# CathodeControl.net
KiCad netlist of a schematic drawn in Altium Designer
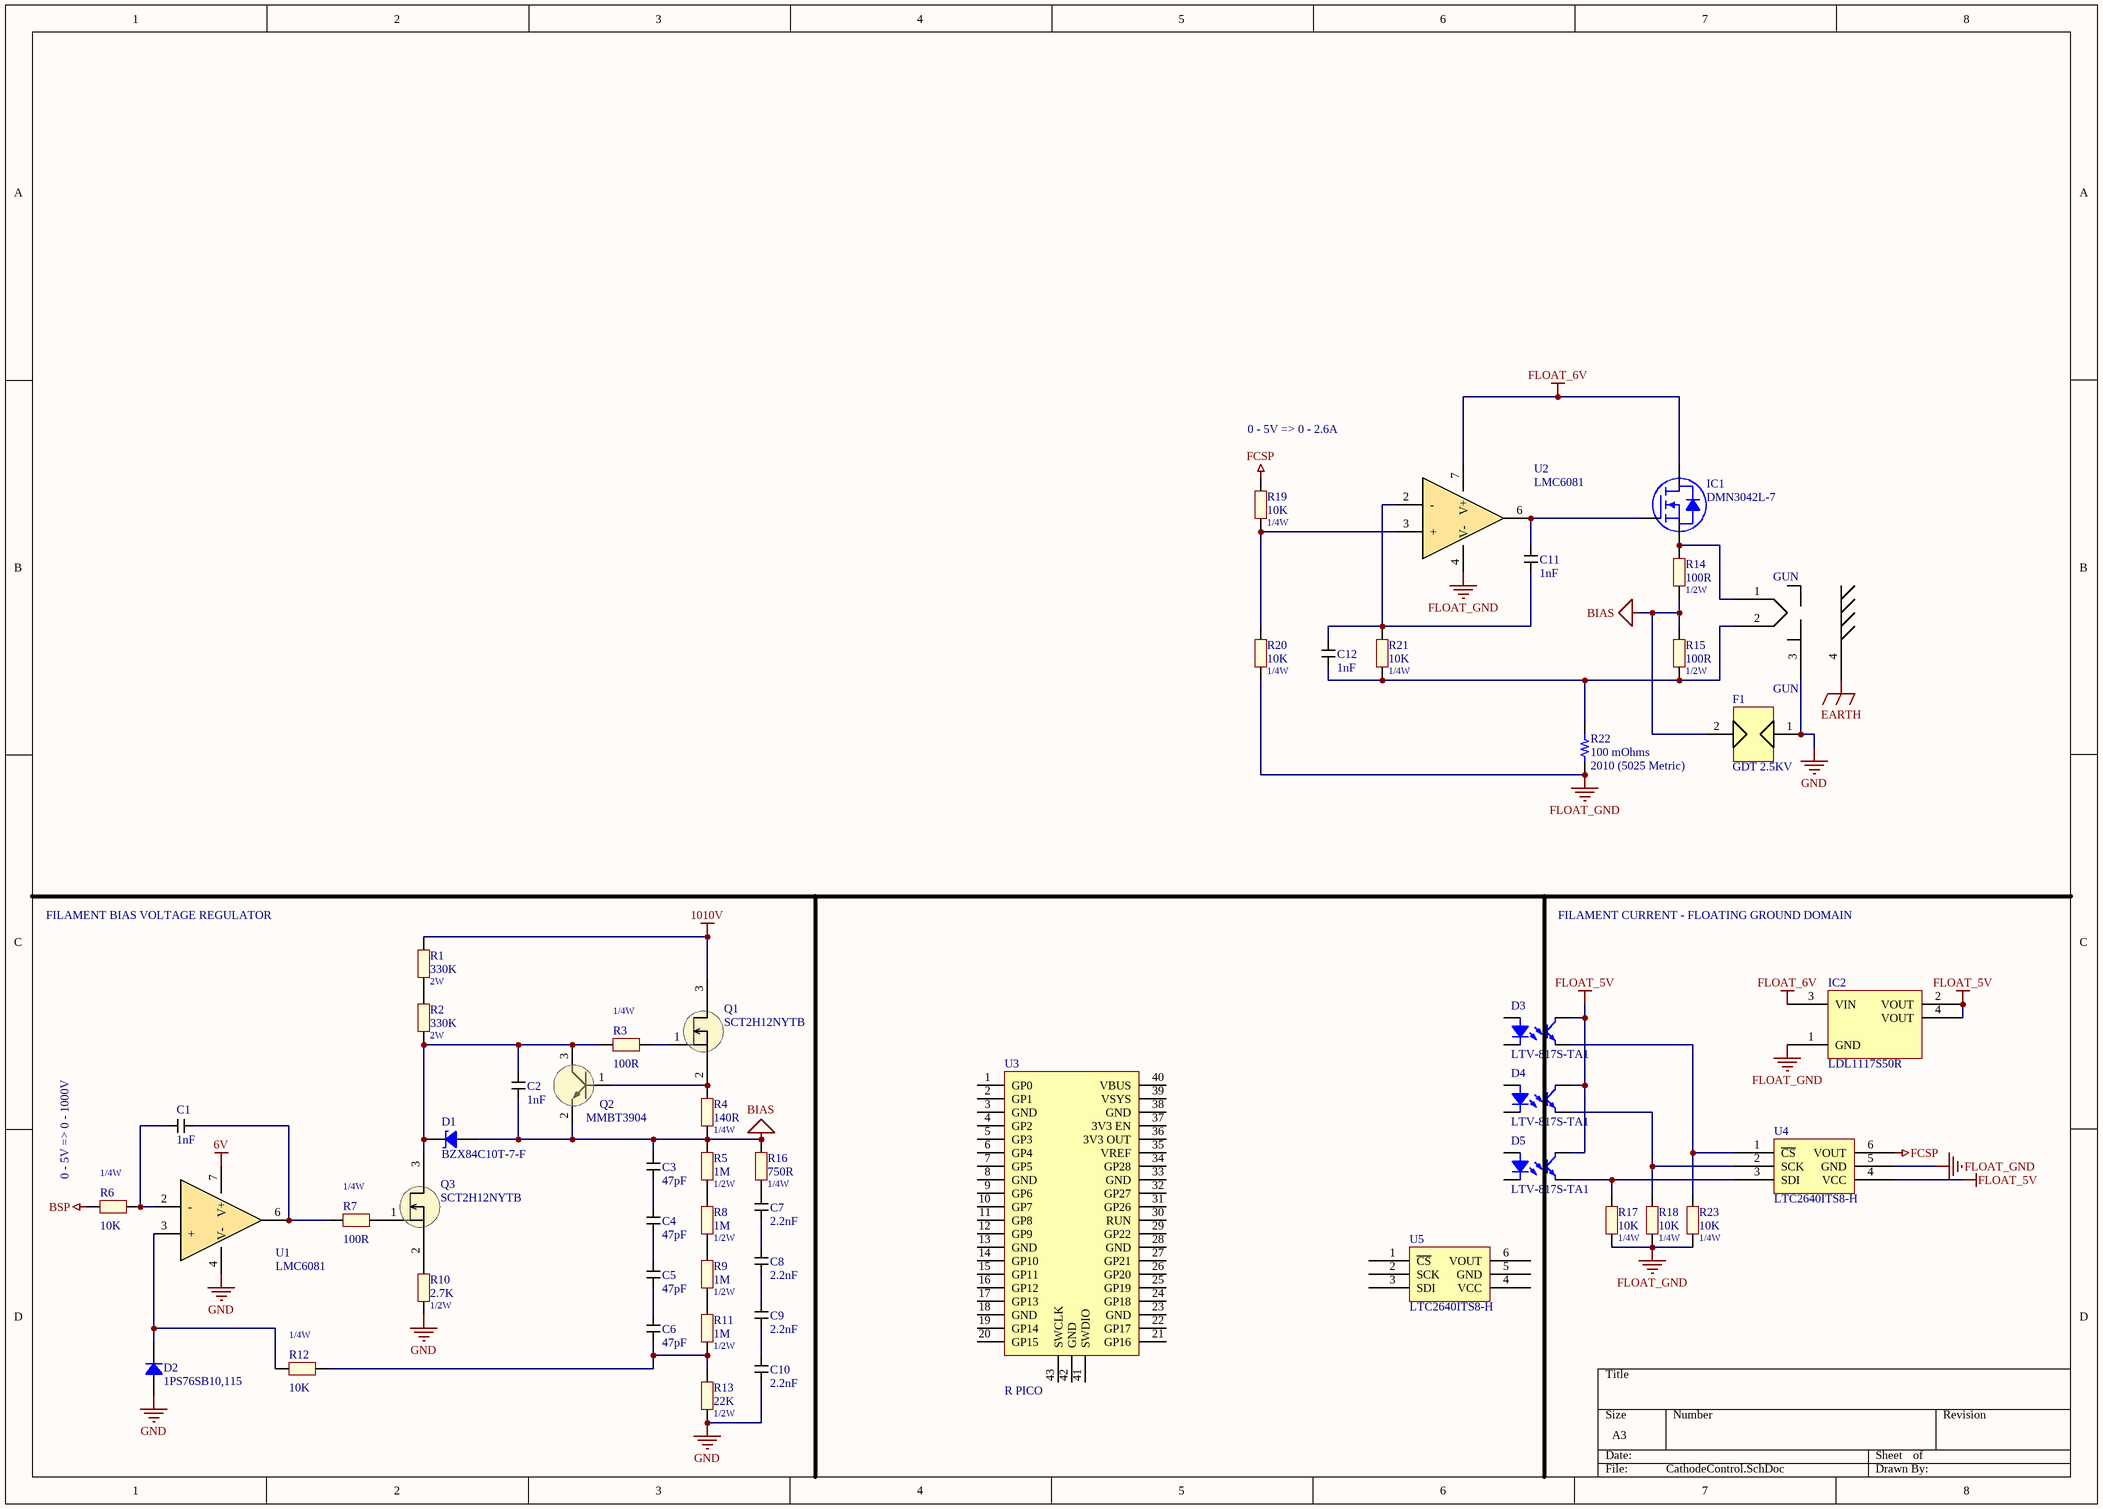
[diagram p0: CathodeControl.SchDoc]

(export (version "E")
  (design (tool "Eeschema 10.0.6"))
  (components
    (comp (ref "C1") (value "1nF") (footprint "C0805") (libsource (lib "VinisLab") (part "C0805")))
    (comp (ref "C2") (value "1nF") (footprint "C0805") (libsource (lib "VinisLab") (part "C0805")))
    (comp (ref "C3")
      (value "47pF")
      (footprint "C0805")
      (description "47 pF ±5% 500V Ceramic Capacitor C0G, NP0 0805 (2012 Metric)")
      (libsource (lib "VinisLab") (part "885342007006"))
    )
    (comp (ref "C4")
      (value "47pF")
      (footprint "C0805")
      (description "47 pF ±5% 500V Ceramic Capacitor C0G, NP0 0805 (2012 Metric)")
      (libsource (lib "VinisLab") (part "885342007006"))
    )
    (comp (ref "C5")
      (value "47pF")
      (footprint "C0805")
      (description "47 pF ±5% 500V Ceramic Capacitor C0G, NP0 0805 (2012 Metric)")
      (libsource (lib "VinisLab") (part "885342007006"))
    )
    (comp (ref "C6")
      (value "47pF")
      (footprint "C0805")
      (description "47 pF ±5% 500V Ceramic Capacitor C0G, NP0 0805 (2012 Metric)")
      (libsource (lib "VinisLab") (part "885342007006"))
    )
    (comp (ref "C7") (value "2.2nF") (footprint "C0805") (libsource (lib "VinisLab") (part "C0805")))
    (comp (ref "C8") (value "2.2nF") (footprint "C0805") (libsource (lib "VinisLab") (part "C0805")))
    (comp (ref "C9") (value "2.2nF") (footprint "C0805") (libsource (lib "VinisLab") (part "C0805")))
    (comp (ref "C10") (value "2.2nF") (footprint "C0805") (libsource (lib "VinisLab") (part "C0805")))
    (comp (ref "C11") (value "1nF") (footprint "C0805") (libsource (lib "VinisLab") (part "C0805")))
    (comp (ref "C12") (value "1nF") (footprint "C0805") (libsource (lib "VinisLab") (part "C0805")))
    (comp (ref "D1")
      (value "BZX84C10T-7-F")
      (footprint "DIODES SOT-523")
      (description "DIODE ZENER 10V 150MW SOT523")
      (fields (field (name "MANUFACTURER") "Diodes Incorporated") (field (name "TOLERANCE") "±6%"))
      (libsource (lib "Cel") (part "Diode Zener"))
    )
    (comp (ref "D2")
      (value "1PS76SB10,115")
      (footprint "SOD323")
      (description "DIODE SCHOTTKY 30V 200MA SOD323")
      (fields (field (name "MANUFACTURER") "Nexperia USA Inc."))
      (libsource (lib "Cel") (part "Diode"))
    )
    (comp (ref "D3")
      (value "LTV-817S-TA1")
      (footprint "LITEON LTV-817")
      (description "OPTOISOLATR 5KV TRANSISTOR 4-SMD")
      (fields (field (name "MANUFACTURER") "Lite-On Inc."))
      (libsource (lib "Cel") (part "Optoisolator"))
    )
    (comp (ref "D4")
      (value "LTV-817S-TA1")
      (footprint "LITEON LTV-817")
      (description "OPTOISOLATR 5KV TRANSISTOR 4-SMD")
      (fields (field (name "MANUFACTURER") "Lite-On Inc."))
      (libsource (lib "Cel") (part "Optoisolator"))
    )
    (comp (ref "D5")
      (value "LTV-817S-TA1")
      (footprint "LITEON LTV-817")
      (description "OPTOISOLATR 5KV TRANSISTOR 4-SMD")
      (fields (field (name "MANUFACTURER") "Lite-On Inc."))
      (libsource (lib "Cel") (part "Optoisolator"))
    )
    (comp (ref "F1")
      (value "GDT 2.5KV")
      (footprint "GDT")
      (description "Gas Discharge Tube 2500 V 2000A (2kA) ±20% 2 Pole Through Hole")
      (libsource (lib "VinisLab") (part "B88069X2500T502"))
    )
    (comp (ref "GUN") (value "GUN") (libsource (lib "VinisLab") (part "GUN")))
    (comp (ref "IC1")
      (value "DMN3042L-7")
      (footprint "DIODES SOT-23-3")
      (description "MOSFET N-CH 30V 5.8A SOT23")
      (fields (field (name "MANUFACTURER") "Diodes Incorporated"))
      (libsource (lib "Cel") (part "DIODES INC MOSFET N-CH SOT-23-3"))
    )
    (comp (ref "IC2")
      (value "LDL1117S50R")
      (footprint "ST SOT-223")
      (description "IC REG LINEAR 5V 1.2A SOT223")
      (fields (field (name "MANUFACTURER") "STMicroelectronics"))
      (libsource (lib "Cel") (part "ST LDL1117"))
    )
    (comp (ref "Q1")
      (value "SCT2H12NYTB")
      (footprint "TO-268-2L")
      (description "N-MOSFET 1700V 4A")
      (libsource (lib "VinisLab") (part "SCT2H12NYTB"))
    )
    (comp (ref "Q2")
      (value "MMBT3904")
      (footprint "SOT-23-3")
      (description "BIPOLAR NPN Transistor")
      (libsource (lib "VinisLab") (part "MMBT3904_1"))
    )
    (comp (ref "Q3")
      (value "SCT2H12NYTB")
      (footprint "TO-268-2L")
      (description "N-MOSFET 1700V 4A")
      (libsource (lib "VinisLab") (part "SCT2H12NYTB"))
    )
    (comp (ref "R1")
      (value "330K")
      (footprint "R2512")
      (description "Resistor 2W")
      (fields (field (name "POWER") "2W"))
      (libsource (lib "VinisLab") (part "R2W"))
    )
    (comp (ref "R2")
      (value "330K")
      (footprint "R2512")
      (description "Resistor 2W")
      (fields (field (name "POWER") "2W"))
      (libsource (lib "VinisLab") (part "R2W"))
    )
    (comp (ref "R3")
      (value "100R")
      (footprint "R0805")
      (description "Resistor 1/2W")
      (fields (field (name "POWER") "1/4W"))
      (libsource (lib "") (part "R0.25W_2"))
    )
    (comp (ref "R4")
      (value "140R")
      (footprint "R0805")
      (description "Resistor 1/2W")
      (fields (field (name "POWER") "1/4W"))
      (libsource (lib "") (part "R0.25W_1"))
    )
    (comp (ref "R5")
      (value "1M")
      (footprint "R1206")
      (description "Resistor 1/2W")
      (fields (field (name "POWER") "1/2W"))
      (libsource (lib "VinisLab") (part "R0.5W"))
    )
    (comp (ref "R6")
      (value "10K")
      (footprint "R0805")
      (description "Resistor 1/2W")
      (fields (field (name "POWER") "1/4W"))
      (libsource (lib "") (part "R0.25W_2"))
    )
    (comp (ref "R7")
      (value "100R")
      (footprint "R0805")
      (description "Resistor 1/2W")
      (fields (field (name "POWER") "1/4W"))
      (libsource (lib "") (part "R0.25W_2"))
    )
    (comp (ref "R8")
      (value "1M")
      (footprint "R1206")
      (description "Resistor 1/2W")
      (fields (field (name "POWER") "1/2W"))
      (libsource (lib "VinisLab") (part "R0.5W"))
    )
    (comp (ref "R9")
      (value "1M")
      (footprint "R1206")
      (description "Resistor 1/2W")
      (fields (field (name "POWER") "1/2W"))
      (libsource (lib "VinisLab") (part "R0.5W"))
    )
    (comp (ref "R10")
      (value "2.7K")
      (footprint "R1206")
      (description "Resistor 1/2W")
      (fields (field (name "POWER") "1/2W"))
      (libsource (lib "VinisLab") (part "R0.5W"))
    )
    (comp (ref "R11")
      (value "1M")
      (footprint "R1206")
      (description "Resistor 1/2W")
      (fields (field (name "POWER") "1/2W"))
      (libsource (lib "VinisLab") (part "R0.5W"))
    )
    (comp (ref "R12")
      (value "10K")
      (footprint "R0805")
      (description "Resistor 1/2W")
      (fields (field (name "POWER") "1/4W"))
      (libsource (lib "") (part "R0.25W_2"))
    )
    (comp (ref "R13")
      (value "22K")
      (footprint "R1206")
      (description "Resistor 1/2W")
      (fields (field (name "POWER") "1/2W"))
      (libsource (lib "VinisLab") (part "R0.5W"))
    )
    (comp (ref "R14")
      (value "100R")
      (footprint "R1206")
      (description "Resistor 1/2W")
      (fields (field (name "POWER") "1/2W"))
      (libsource (lib "VinisLab") (part "R0.5W"))
    )
    (comp (ref "R15")
      (value "100R")
      (footprint "R1206")
      (description "Resistor 1/2W")
      (fields (field (name "POWER") "1/2W"))
      (libsource (lib "VinisLab") (part "R0.5W"))
    )
    (comp (ref "R16")
      (value "750R")
      (footprint "R0805")
      (description "Resistor 1/2W")
      (fields (field (name "POWER") "1/4W"))
      (libsource (lib "VinisLab") (part "R0.25W"))
    )
    (comp (ref "R17")
      (value "10K")
      (footprint "R0805")
      (description "Resistor 1/2W")
      (fields (field (name "POWER") "1/4W"))
      (libsource (lib "VinisLab") (part "R0.25W"))
    )
    (comp (ref "R18")
      (value "10K")
      (footprint "R0805")
      (description "Resistor 1/2W")
      (fields (field (name "POWER") "1/4W"))
      (libsource (lib "VinisLab") (part "R0.25W"))
    )
    (comp (ref "R19")
      (value "10K")
      (footprint "R0805")
      (description "Resistor 1/2W")
      (fields (field (name "POWER") "1/4W"))
      (libsource (lib "VinisLab") (part "R0.25W"))
    )
    (comp (ref "R20")
      (value "10K")
      (footprint "R0805")
      (description "Resistor 1/2W")
      (fields (field (name "POWER") "1/4W"))
      (libsource (lib "VinisLab") (part "R0.25W"))
    )
    (comp (ref "R21")
      (value "10K")
      (footprint "R0805")
      (description "Resistor 1/2W")
      (fields (field (name "POWER") "1/4W"))
      (libsource (lib "VinisLab") (part "R0.25W"))
    )
    (comp (ref "R22")
      (value "100 mOhms")
      (footprint "STACKPOLE CSR2010")
      (description "RES 0.1 OHM 2W 2010 WIDE")
      (fields
        (field (name "PART NUMBER") "ERJ-B1CFR10U")
        (field (name "PACKAGE / CASE") "2010 (5025 Metric)")
        (field (name "MANUFACTURER") "Panasonic Electronic Components")
      )
      (libsource (lib "Cel") (part "Resistor"))
    )
    (comp (ref "R23")
      (value "10K")
      (footprint "R0805")
      (description "Resistor 1/2W")
      (fields (field (name "POWER") "1/4W"))
      (libsource (lib "VinisLab") (part "R0.25W"))
    )
    (comp (ref "U1") (value "LMC6081") (footprint "SOIC-8") (libsource (lib "VinisLab") (part "LMC6081")))
    (comp (ref "U2") (value "LMC6081") (footprint "SOIC-8") (libsource (lib "VinisLab") (part "LMC6081")))
    (comp (ref "U3") (value "R PICO") (footprint "RPICO") (libsource (lib "VinisLab") (part "RaspPico")))
    (comp (ref "U4")
      (value "LTC2640ITS8-H")
      (footprint "SC-70-6")
      (libsource (lib "VinisLab") (part "LTC2640ITS8-HZ12"))
    )
    (comp (ref "U5")
      (value "LTC2640ITS8-H")
      (footprint "SC-70-6")
      (libsource (lib "VinisLab") (part "LTC2640ITS8-HZ12"))
    )
  )
  (nets
    (net (code "1") (name "6V") (class "Default")
      (node (ref "U1") (pin "7") (pinfunction "V+_7") (pintype "passive"))
    )
    (net (code "2") (name "1010V") (class "Default")
      (node (ref "Q1") (pin "3") (pintype "passive"))
      (node (ref "R1") (pin "2") (pintype "passive"))
    )
    (net (code "3") (name "BIAS") (class "Default")
      (node (ref "C2") (pin "1") (pintype "passive"))
      (node (ref "C3") (pin "2") (pintype "passive"))
      (node (ref "D1") (pin "1") (pinfunction "1_1") (pintype "passive"))
      (node (ref "F1") (pin "2") (pintype "passive"))
      (node (ref "Q2") (pin "2") (pintype "passive"))
      (node (ref "R14") (pin "1") (pintype "passive"))
      (node (ref "R15") (pin "2") (pintype "passive"))
      (node (ref "R16") (pin "1") (pintype "passive"))
      (node (ref "R4") (pin "1") (pintype "passive"))
      (node (ref "R5") (pin "2") (pintype "passive"))
    )
    (net (code "4") (name "BSP") (class "Default") (node (ref "R6") (pin "2") (pintype "passive")))
    (net (code "5") (name "EARTH") (class "Default") (node (ref "GUN") (pin "4") (pintype "passive")))
    (net (code "6") (name "FCSP") (class "Default")
      (node (ref "R19") (pin "1") (pintype "passive"))
      (node (ref "U4") (pin "6") (pinfunction "VOUT_6") (pintype "passive"))
    )
    (net (code "7") (name "FLOAT_5V") (class "Default")
      (node (ref "D3") (pin "4") (pinfunction "4_4") (pintype "passive"))
      (node (ref "D4") (pin "4") (pinfunction "4_4") (pintype "passive"))
      (node (ref "D5") (pin "4") (pinfunction "4_4") (pintype "passive"))
      (node (ref "IC2") (pin "2") (pinfunction "VOUT_2") (pintype "passive"))
      (node (ref "IC2") (pin "4") (pinfunction "VOUT_4") (pintype "passive"))
      (node (ref "U4") (pin "4") (pinfunction "VCC_4") (pintype "passive"))
    )
    (net (code "8") (name "FLOAT_6V") (class "Default")
      (node (ref "IC1") (pin "3") (pinfunction "D_3") (pintype "passive"))
      (node (ref "IC2") (pin "3") (pinfunction "VIN_3") (pintype "passive"))
      (node (ref "U2") (pin "7") (pinfunction "V+_7") (pintype "passive"))
    )
    (net (code "9") (name "FLOAT_GND") (class "Default")
      (node (ref "IC2") (pin "1") (pinfunction "GND_1") (pintype "passive"))
      (node (ref "R17") (pin "2") (pintype "passive"))
      (node (ref "R18") (pin "2") (pintype "passive"))
      (node (ref "R20") (pin "2") (pintype "passive"))
      (node (ref "R22") (pin "1") (pinfunction "1_1") (pintype "passive"))
      (node (ref "R23") (pin "2") (pintype "passive"))
      (node (ref "U2") (pin "4") (pinfunction "V-_4") (pintype "passive"))
      (node (ref "U4") (pin "5") (pinfunction "GND_5") (pintype "passive"))
    )
    (net (code "10") (name "GND") (class "Default")
      (node (ref "C10") (pin "1") (pintype "passive"))
      (node (ref "D2") (pin "1") (pinfunction "1_1") (pintype "passive"))
      (node (ref "F1") (pin "1") (pintype "passive"))
      (node (ref "GUN") (pin "3") (pintype "passive"))
      (node (ref "R10") (pin "1") (pintype "passive"))
      (node (ref "R13") (pin "1") (pintype "passive"))
      (node (ref "U1") (pin "4") (pinfunction "V-_4") (pintype "passive"))
    )
    (net (code "11") (name "Net-(C1-Pad1)") (class "Default")
      (node (ref "C1") (pin "1") (pintype "passive"))
      (node (ref "R7") (pin "2") (pintype "passive"))
      (node (ref "U1") (pin "6") (pintype "passive"))
    )
    (net (code "12") (name "Net-(C2-Pad2)") (class "Default")
      (node (ref "C2") (pin "2") (pintype "passive"))
      (node (ref "D1") (pin "2") (pinfunction "2_2") (pintype "passive"))
      (node (ref "Q2") (pin "3") (pintype "passive"))
      (node (ref "Q3") (pin "3") (pintype "passive"))
      (node (ref "R2") (pin "1") (pintype "passive"))
      (node (ref "R3") (pin "2") (pintype "passive"))
    )
    (net (code "13") (name "Net-(C3-Pad1)") (class "Default")
      (node (ref "C3") (pin "1") (pintype "passive"))
      (node (ref "C4") (pin "2") (pintype "passive"))
    )
    (net (code "14") (name "Net-(C4-Pad1)") (class "Default")
      (node (ref "C4") (pin "1") (pintype "passive"))
      (node (ref "C5") (pin "2") (pintype "passive"))
    )
    (net (code "15") (name "Net-(C5-Pad1)") (class "Default")
      (node (ref "C5") (pin "1") (pintype "passive"))
      (node (ref "C6") (pin "2") (pintype "passive"))
    )
    (net (code "16") (name "Net-(C6-Pad1)") (class "Default")
      (node (ref "C6") (pin "1") (pintype "passive"))
      (node (ref "R11") (pin "1") (pintype "passive"))
      (node (ref "R12") (pin "1") (pintype "passive"))
      (node (ref "R13") (pin "2") (pintype "passive"))
    )
    (net (code "17") (name "Net-(C7-Pad1)") (class "Default")
      (node (ref "C7") (pin "1") (pintype "passive"))
      (node (ref "C8") (pin "2") (pintype "passive"))
    )
    (net (code "18") (name "Net-(C7-Pad2)") (class "Default")
      (node (ref "C7") (pin "2") (pintype "passive"))
      (node (ref "R16") (pin "2") (pintype "passive"))
    )
    (net (code "19") (name "Net-(C8-Pad1)") (class "Default")
      (node (ref "C8") (pin "1") (pintype "passive"))
      (node (ref "C9") (pin "2") (pintype "passive"))
    )
    (net (code "20") (name "Net-(C10-Pad2)") (class "Default")
      (node (ref "C10") (pin "2") (pintype "passive"))
      (node (ref "C9") (pin "1") (pintype "passive"))
    )
    (net (code "21") (name "Net-(C12-Pad2)") (class "Default")
      (node (ref "C12") (pin "2") (pintype "passive"))
      (node (ref "GUN") (pin "2") (pintype "passive"))
      (node (ref "R15") (pin "1") (pintype "passive"))
      (node (ref "R21") (pin "2") (pintype "passive"))
      (node (ref "R22") (pin "2") (pinfunction "2_2") (pintype "passive"))
    )
    (net (code "22") (name "Net-(IC1-G)") (class "Default")
      (node (ref "C11") (pin "1") (pintype "passive"))
      (node (ref "IC1") (pin "1") (pinfunction "G_1") (pintype "passive"))
      (node (ref "U2") (pin "6") (pintype "passive"))
    )
    (net (code "23") (name "Net-(IC1-S)") (class "Default")
      (node (ref "GUN") (pin "1") (pintype "passive"))
      (node (ref "IC1") (pin "2") (pinfunction "S_2") (pintype "passive"))
      (node (ref "R14") (pin "2") (pintype "passive"))
    )
    (net (code "24") (name "Net-(Q1-Pad1)") (class "Default")
      (node (ref "Q1") (pin "1") (pintype "passive"))
      (node (ref "R3") (pin "1") (pintype "passive"))
    )
    (net (code "25") (name "Net-(Q1-Pad2)") (class "Default")
      (node (ref "Q1") (pin "2") (pintype "passive"))
      (node (ref "Q2") (pin "1") (pintype "passive"))
      (node (ref "R4") (pin "2") (pintype "passive"))
    )
    (net (code "26") (name "Net-(Q3-Pad1)") (class "Default")
      (node (ref "Q3") (pin "1") (pintype "passive"))
      (node (ref "R7") (pin "1") (pintype "passive"))
    )
    (net (code "27") (name "Net-(Q3-Pad2)") (class "Default")
      (node (ref "Q3") (pin "2") (pintype "passive"))
      (node (ref "R10") (pin "2") (pintype "passive"))
    )
    (net (code "28") (name "Net-(R1-Pad1)") (class "Default")
      (node (ref "R1") (pin "1") (pintype "passive"))
      (node (ref "R2") (pin "2") (pintype "passive"))
    )
    (net (code "29") (name "Net-(R5-Pad1)") (class "Default")
      (node (ref "R5") (pin "1") (pintype "passive"))
      (node (ref "R8") (pin "2") (pintype "passive"))
    )
    (net (code "30") (name "Net-(R8-Pad1)") (class "Default")
      (node (ref "R8") (pin "1") (pintype "passive"))
      (node (ref "R9") (pin "2") (pintype "passive"))
    )
    (net (code "31") (name "Net-(R11-Pad2)") (class "Default")
      (node (ref "R11") (pin "2") (pintype "passive"))
      (node (ref "R9") (pin "1") (pintype "passive"))
    )
    (net (code "32") (name "Net-(U1-+)") (class "Default")
      (node (ref "D2") (pin "2") (pinfunction "2_2") (pintype "passive"))
      (node (ref "R12") (pin "2") (pintype "passive"))
      (node (ref "U1") (pin "3") (pinfunction "+_3") (pintype "passive"))
    )
    (net (code "33") (name "Net-(U1--)") (class "Default")
      (node (ref "C1") (pin "2") (pintype "passive"))
      (node (ref "R6") (pin "1") (pintype "passive"))
      (node (ref "U1") (pin "2") (pinfunction "-_2") (pintype "passive"))
    )
    (net (code "34") (name "Net-(U2-+)") (class "Default")
      (node (ref "R19") (pin "2") (pintype "passive"))
      (node (ref "R20") (pin "1") (pintype "passive"))
      (node (ref "U2") (pin "3") (pinfunction "+_3") (pintype "passive"))
    )
    (net (code "35") (name "Net-(U2--)") (class "Default")
      (node (ref "C11") (pin "2") (pintype "passive"))
      (node (ref "C12") (pin "1") (pintype "passive"))
      (node (ref "R21") (pin "1") (pintype "passive"))
      (node (ref "U2") (pin "2") (pinfunction "-_2") (pintype "passive"))
    )
    (net (code "36") (name "Net-(U4-SCK)") (class "Default")
      (node (ref "D4") (pin "3") (pinfunction "3_3") (pintype "passive"))
      (node (ref "R18") (pin "1") (pintype "passive"))
      (node (ref "U4") (pin "2") (pinfunction "SCK_2") (pintype "passive"))
    )
    (net (code "37") (name "Net-(U4-SDI)") (class "Default")
      (node (ref "D5") (pin "3") (pinfunction "3_3") (pintype "passive"))
      (node (ref "R17") (pin "1") (pintype "passive"))
      (node (ref "U4") (pin "3") (pinfunction "SDI_3") (pintype "passive"))
    )
    (net (code "38") (name "Net-(U4-~{CS})") (class "Default")
      (node (ref "D3") (pin "3") (pinfunction "3_3") (pintype "passive"))
      (node (ref "R23") (pin "1") (pintype "passive"))
      (node (ref "U4") (pin "1") (pinfunction "~{CS}_1") (pintype "passive"))
    )
    (net (code "39") (name "unconnected-(D3-Pad1)") (class "Default")
      (node (ref "D3") (pin "1") (pinfunction "1_1") (pintype "passive"))
    )
    (net (code "40") (name "unconnected-(D3-Pad2)") (class "Default")
      (node (ref "D3") (pin "2") (pinfunction "2_2") (pintype "passive"))
    )
    (net (code "41") (name "unconnected-(D4-Pad1)") (class "Default")
      (node (ref "D4") (pin "1") (pinfunction "1_1") (pintype "passive"))
    )
    (net (code "42") (name "unconnected-(D4-Pad2)") (class "Default")
      (node (ref "D4") (pin "2") (pinfunction "2_2") (pintype "passive"))
    )
    (net (code "43") (name "unconnected-(D5-Pad1)") (class "Default")
      (node (ref "D5") (pin "1") (pinfunction "1_1") (pintype "passive"))
    )
    (net (code "44") (name "unconnected-(D5-Pad2)") (class "Default")
      (node (ref "D5") (pin "2") (pinfunction "2_2") (pintype "passive"))
    )
    (net (code "45") (name "unconnected-(U3-3V3_EN-Pad37)") (class "Default")
      (node (ref "U3") (pin "37") (pinfunction "3V3_EN_37") (pintype "passive"))
    )
    (net (code "46") (name "unconnected-(U3-3V3_OUT-Pad36)") (class "Default")
      (node (ref "U3") (pin "36") (pinfunction "3V3_OUT_36") (pintype "passive"))
    )
    (net (code "47") (name "unconnected-(U3-GND-Pad3)") (class "Default")
      (node (ref "U3") (pin "3") (pinfunction "GND_3") (pintype "passive"))
    )
    (net (code "48") (name "unconnected-(U3-GND-Pad8)") (class "Default")
      (node (ref "U3") (pin "8") (pinfunction "GND_8") (pintype "passive"))
    )
    (net (code "49") (name "unconnected-(U3-GND-Pad13)") (class "Default")
      (node (ref "U3") (pin "13") (pinfunction "GND_13") (pintype "passive"))
    )
    (net (code "50") (name "unconnected-(U3-GND-Pad18)") (class "Default")
      (node (ref "U3") (pin "18") (pinfunction "GND_18") (pintype "passive"))
    )
    (net (code "51") (name "unconnected-(U3-GND-Pad23)") (class "Default")
      (node (ref "U3") (pin "23") (pinfunction "GND_23") (pintype "passive"))
    )
    (net (code "52") (name "unconnected-(U3-GND-Pad28)") (class "Default")
      (node (ref "U3") (pin "28") (pinfunction "GND_28") (pintype "passive"))
    )
    (net (code "53") (name "unconnected-(U3-GND-Pad33)") (class "Default")
      (node (ref "U3") (pin "33") (pinfunction "GND_33") (pintype "passive"))
    )
    (net (code "54") (name "unconnected-(U3-GND-Pad38)") (class "Default")
      (node (ref "U3") (pin "38") (pinfunction "GND_38") (pintype "passive"))
    )
    (net (code "55") (name "unconnected-(U3-GND-Pad42)") (class "Default")
      (node (ref "U3") (pin "42") (pinfunction "GND_42") (pintype "passive"))
    )
    (net (code "56") (name "unconnected-(U3-GP0-Pad1)") (class "Default")
      (node (ref "U3") (pin "1") (pinfunction "GP0_1") (pintype "passive"))
    )
    (net (code "57") (name "unconnected-(U3-GP1-Pad2)") (class "Default")
      (node (ref "U3") (pin "2") (pinfunction "GP1_2") (pintype "passive"))
    )
    (net (code "58") (name "unconnected-(U3-GP2-Pad4)") (class "Default")
      (node (ref "U3") (pin "4") (pinfunction "GP2_4") (pintype "passive"))
    )
    (net (code "59") (name "unconnected-(U3-GP3-Pad5)") (class "Default")
      (node (ref "U3") (pin "5") (pinfunction "GP3_5") (pintype "passive"))
    )
    (net (code "60") (name "unconnected-(U3-GP4-Pad6)") (class "Default")
      (node (ref "U3") (pin "6") (pinfunction "GP4_6") (pintype "passive"))
    )
    (net (code "61") (name "unconnected-(U3-GP5-Pad7)") (class "Default")
      (node (ref "U3") (pin "7") (pinfunction "GP5_7") (pintype "passive"))
    )
    (net (code "62") (name "unconnected-(U3-GP6-Pad9)") (class "Default")
      (node (ref "U3") (pin "9") (pinfunction "GP6_9") (pintype "passive"))
    )
    (net (code "63") (name "unconnected-(U3-GP7-Pad10)") (class "Default")
      (node (ref "U3") (pin "10") (pinfunction "GP7_10") (pintype "passive"))
    )
    (net (code "64") (name "unconnected-(U3-GP8-Pad11)") (class "Default")
      (node (ref "U3") (pin "11") (pinfunction "GP8_11") (pintype "passive"))
    )
    (net (code "65") (name "unconnected-(U3-GP9-Pad12)") (class "Default")
      (node (ref "U3") (pin "12") (pinfunction "GP9_12") (pintype "passive"))
    )
    (net (code "66") (name "unconnected-(U3-GP10-Pad14)") (class "Default")
      (node (ref "U3") (pin "14") (pinfunction "GP10_14") (pintype "passive"))
    )
    (net (code "67") (name "unconnected-(U3-GP11-Pad15)") (class "Default")
      (node (ref "U3") (pin "15") (pinfunction "GP11_15") (pintype "passive"))
    )
    (net (code "68") (name "unconnected-(U3-GP12-Pad16)") (class "Default")
      (node (ref "U3") (pin "16") (pinfunction "GP12_16") (pintype "passive"))
    )
    (net (code "69") (name "unconnected-(U3-GP13-Pad17)") (class "Default")
      (node (ref "U3") (pin "17") (pinfunction "GP13_17") (pintype "passive"))
    )
    (net (code "70") (name "unconnected-(U3-GP14-Pad19)") (class "Default")
      (node (ref "U3") (pin "19") (pinfunction "GP14_19") (pintype "passive"))
    )
    (net (code "71") (name "unconnected-(U3-GP15-Pad20)") (class "Default")
      (node (ref "U3") (pin "20") (pinfunction "GP15_20") (pintype "passive"))
    )
    (net (code "72") (name "unconnected-(U3-GP16-Pad21)") (class "Default")
      (node (ref "U3") (pin "21") (pinfunction "GP16_21") (pintype "passive"))
    )
    (net (code "73") (name "unconnected-(U3-GP17-Pad22)") (class "Default")
      (node (ref "U3") (pin "22") (pinfunction "GP17_22") (pintype "passive"))
    )
    (net (code "74") (name "unconnected-(U3-GP18-Pad24)") (class "Default")
      (node (ref "U3") (pin "24") (pinfunction "GP18_24") (pintype "passive"))
    )
    (net (code "75") (name "unconnected-(U3-GP19-Pad25)") (class "Default")
      (node (ref "U3") (pin "25") (pinfunction "GP19_25") (pintype "passive"))
    )
    (net (code "76") (name "unconnected-(U3-GP20-Pad26)") (class "Default")
      (node (ref "U3") (pin "26") (pinfunction "GP20_26") (pintype "passive"))
    )
    (net (code "77") (name "unconnected-(U3-GP21-Pad27)") (class "Default")
      (node (ref "U3") (pin "27") (pinfunction "GP21_27") (pintype "passive"))
    )
    (net (code "78") (name "unconnected-(U3-GP22-Pad29)") (class "Default")
      (node (ref "U3") (pin "29") (pinfunction "GP22_29") (pintype "passive"))
    )
    (net (code "79") (name "unconnected-(U3-GP26-Pad31)") (class "Default")
      (node (ref "U3") (pin "31") (pinfunction "GP26_31") (pintype "passive"))
    )
    (net (code "80") (name "unconnected-(U3-GP27-Pad32)") (class "Default")
      (node (ref "U3") (pin "32") (pinfunction "GP27_32") (pintype "passive"))
    )
    (net (code "81") (name "unconnected-(U3-GP28-Pad34)") (class "Default")
      (node (ref "U3") (pin "34") (pinfunction "GP28_34") (pintype "passive"))
    )
    (net (code "82") (name "unconnected-(U3-RUN-Pad30)") (class "Default")
      (node (ref "U3") (pin "30") (pinfunction "RUN_30") (pintype "passive"))
    )
    (net (code "83") (name "unconnected-(U3-SWCLK-Pad43)") (class "Default")
      (node (ref "U3") (pin "43") (pinfunction "SWCLK_43") (pintype "passive"))
    )
    (net (code "84") (name "unconnected-(U3-SWDIO-Pad41)") (class "Default")
      (node (ref "U3") (pin "41") (pinfunction "SWDIO_41") (pintype "passive"))
    )
    (net (code "85") (name "unconnected-(U3-VBUS-Pad40)") (class "Default")
      (node (ref "U3") (pin "40") (pinfunction "VBUS_40") (pintype "passive"))
    )
    (net (code "86") (name "unconnected-(U3-VREF-Pad35)") (class "Default")
      (node (ref "U3") (pin "35") (pinfunction "VREF_35") (pintype "passive"))
    )
    (net (code "87") (name "unconnected-(U3-VSYS-Pad39)") (class "Default")
      (node (ref "U3") (pin "39") (pinfunction "VSYS_39") (pintype "passive"))
    )
    (net (code "88") (name "unconnected-(U5-GND-Pad5)") (class "Default")
      (node (ref "U5") (pin "5") (pinfunction "GND_5") (pintype "passive"))
    )
    (net (code "89") (name "unconnected-(U5-SCK-Pad2)") (class "Default")
      (node (ref "U5") (pin "2") (pinfunction "SCK_2") (pintype "passive"))
    )
    (net (code "90") (name "unconnected-(U5-SDI-Pad3)") (class "Default")
      (node (ref "U5") (pin "3") (pinfunction "SDI_3") (pintype "passive"))
    )
    (net (code "91") (name "unconnected-(U5-VCC-Pad4)") (class "Default")
      (node (ref "U5") (pin "4") (pinfunction "VCC_4") (pintype "passive"))
    )
    (net (code "92") (name "unconnected-(U5-VOUT-Pad6)") (class "Default")
      (node (ref "U5") (pin "6") (pinfunction "VOUT_6") (pintype "passive"))
    )
    (net (code "93") (name "unconnected-(U5-~{CS}-Pad1)") (class "Default")
      (node (ref "U5") (pin "1") (pinfunction "~{CS}_1") (pintype "passive"))
    )
  )
)
